# Tugas1.net
KiCad netlist of a schematic drawn in EAGLE
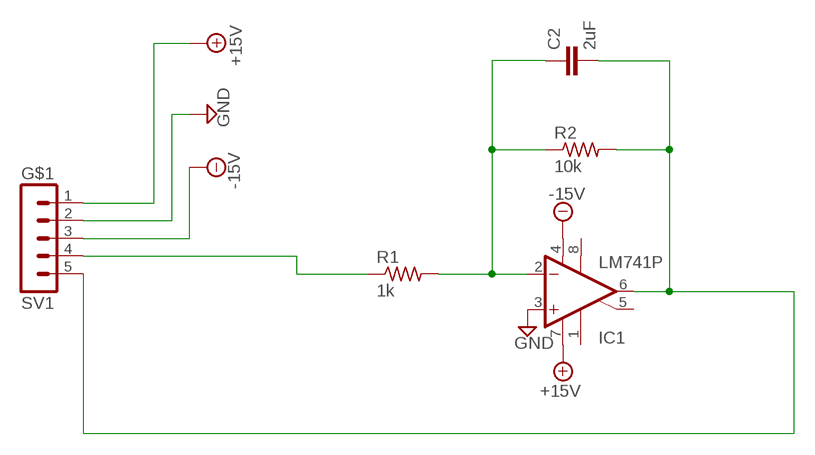
[diagram p0: schematic, sheet 1]

(export (version "E")
  (design (tool "Eeschema 10.0.6"))
  (components
    (comp (ref "C2")
      (value "2uF")
      (footprint "eagle-import:C0603")
      (libsource (lib "eagle-import") (part "C-EUC0603"))
    )
    (comp (ref "IC1")
      (value "LM741P")
      (footprint "eagle-import:DIL08")
      (libsource (lib "eagle-import") (part "741PLM"))
    )
    (comp (ref "R1")
      (value "1k")
      (footprint "eagle-import:R0603")
      (libsource (lib "eagle-import") (part "R-US_R0603"))
    )
    (comp (ref "R2")
      (value "10k")
      (footprint "eagle-import:R0603")
      (libsource (lib "eagle-import") (part "R-US_R0603"))
    )
    (comp (ref "SV1")
      (value "G$1")
      (footprint "eagle-import:MA05-1")
      (libsource (lib "eagle-import") (part "MA05-1"))
    )
  )
  (nets
    (net (code "1") (name "+15V") (class "Default")
      (node (ref "IC1") (pin "7") (pinfunction "V+_7") (pintype "power_in"))
      (node (ref "SV1") (pin "1") (pinfunction "1_1") (pintype "passive"))
    )
    (net (code "2") (name "-15V") (class "Default")
      (node (ref "IC1") (pin "4") (pinfunction "V-_4") (pintype "power_in"))
      (node (ref "SV1") (pin "3") (pinfunction "3_3") (pintype "passive"))
    )
    (net (code "3") (name "GND") (class "Default")
      (node (ref "IC1") (pin "3") (pinfunction "+IN_3") (pintype "input"))
      (node (ref "SV1") (pin "2") (pinfunction "2_2") (pintype "passive"))
    )
    (net (code "4") (name "Net-(IC1--IN)") (class "Default")
      (node (ref "C2") (pin "1") (pinfunction "1_1") (pintype "passive"))
      (node (ref "IC1") (pin "2") (pinfunction "-IN_2") (pintype "input"))
      (node (ref "R1") (pin "2") (pinfunction "2_2") (pintype "passive"))
      (node (ref "R2") (pin "1") (pinfunction "1_1") (pintype "passive"))
    )
    (net (code "5") (name "Net-(IC1-OUT)") (class "Default")
      (node (ref "C2") (pin "2") (pinfunction "2_2") (pintype "passive"))
      (node (ref "IC1") (pin "6") (pinfunction "OUT_6") (pintype "output"))
      (node (ref "R2") (pin "2") (pinfunction "2_2") (pintype "passive"))
      (node (ref "SV1") (pin "5") (pinfunction "5_5") (pintype "passive"))
    )
    (net (code "6") (name "Net-(R1-Pad1)") (class "Default")
      (node (ref "R1") (pin "1") (pinfunction "1_1") (pintype "passive"))
      (node (ref "SV1") (pin "4") (pinfunction "4_4") (pintype "passive"))
    )
    (net (code "7") (name "unconnected-(IC1-ON1-Pad1)") (class "Default")
      (node (ref "IC1") (pin "1") (pinfunction "ON1_1") (pintype "passive"))
    )
    (net (code "8") (name "unconnected-(IC1-ON2-Pad5)") (class "Default")
      (node (ref "IC1") (pin "5") (pinfunction "ON2_5") (pintype "passive"))
    )
    (net (code "9") (name "unconnected-(IC1-OPT-Pad8)") (class "Default")
      (node (ref "IC1") (pin "8") (pinfunction "OPT_8") (pintype "passive"))
    )
  )
)
